# pulse-generator.net
KiCad netlist of a schematic drawn in EAGLE
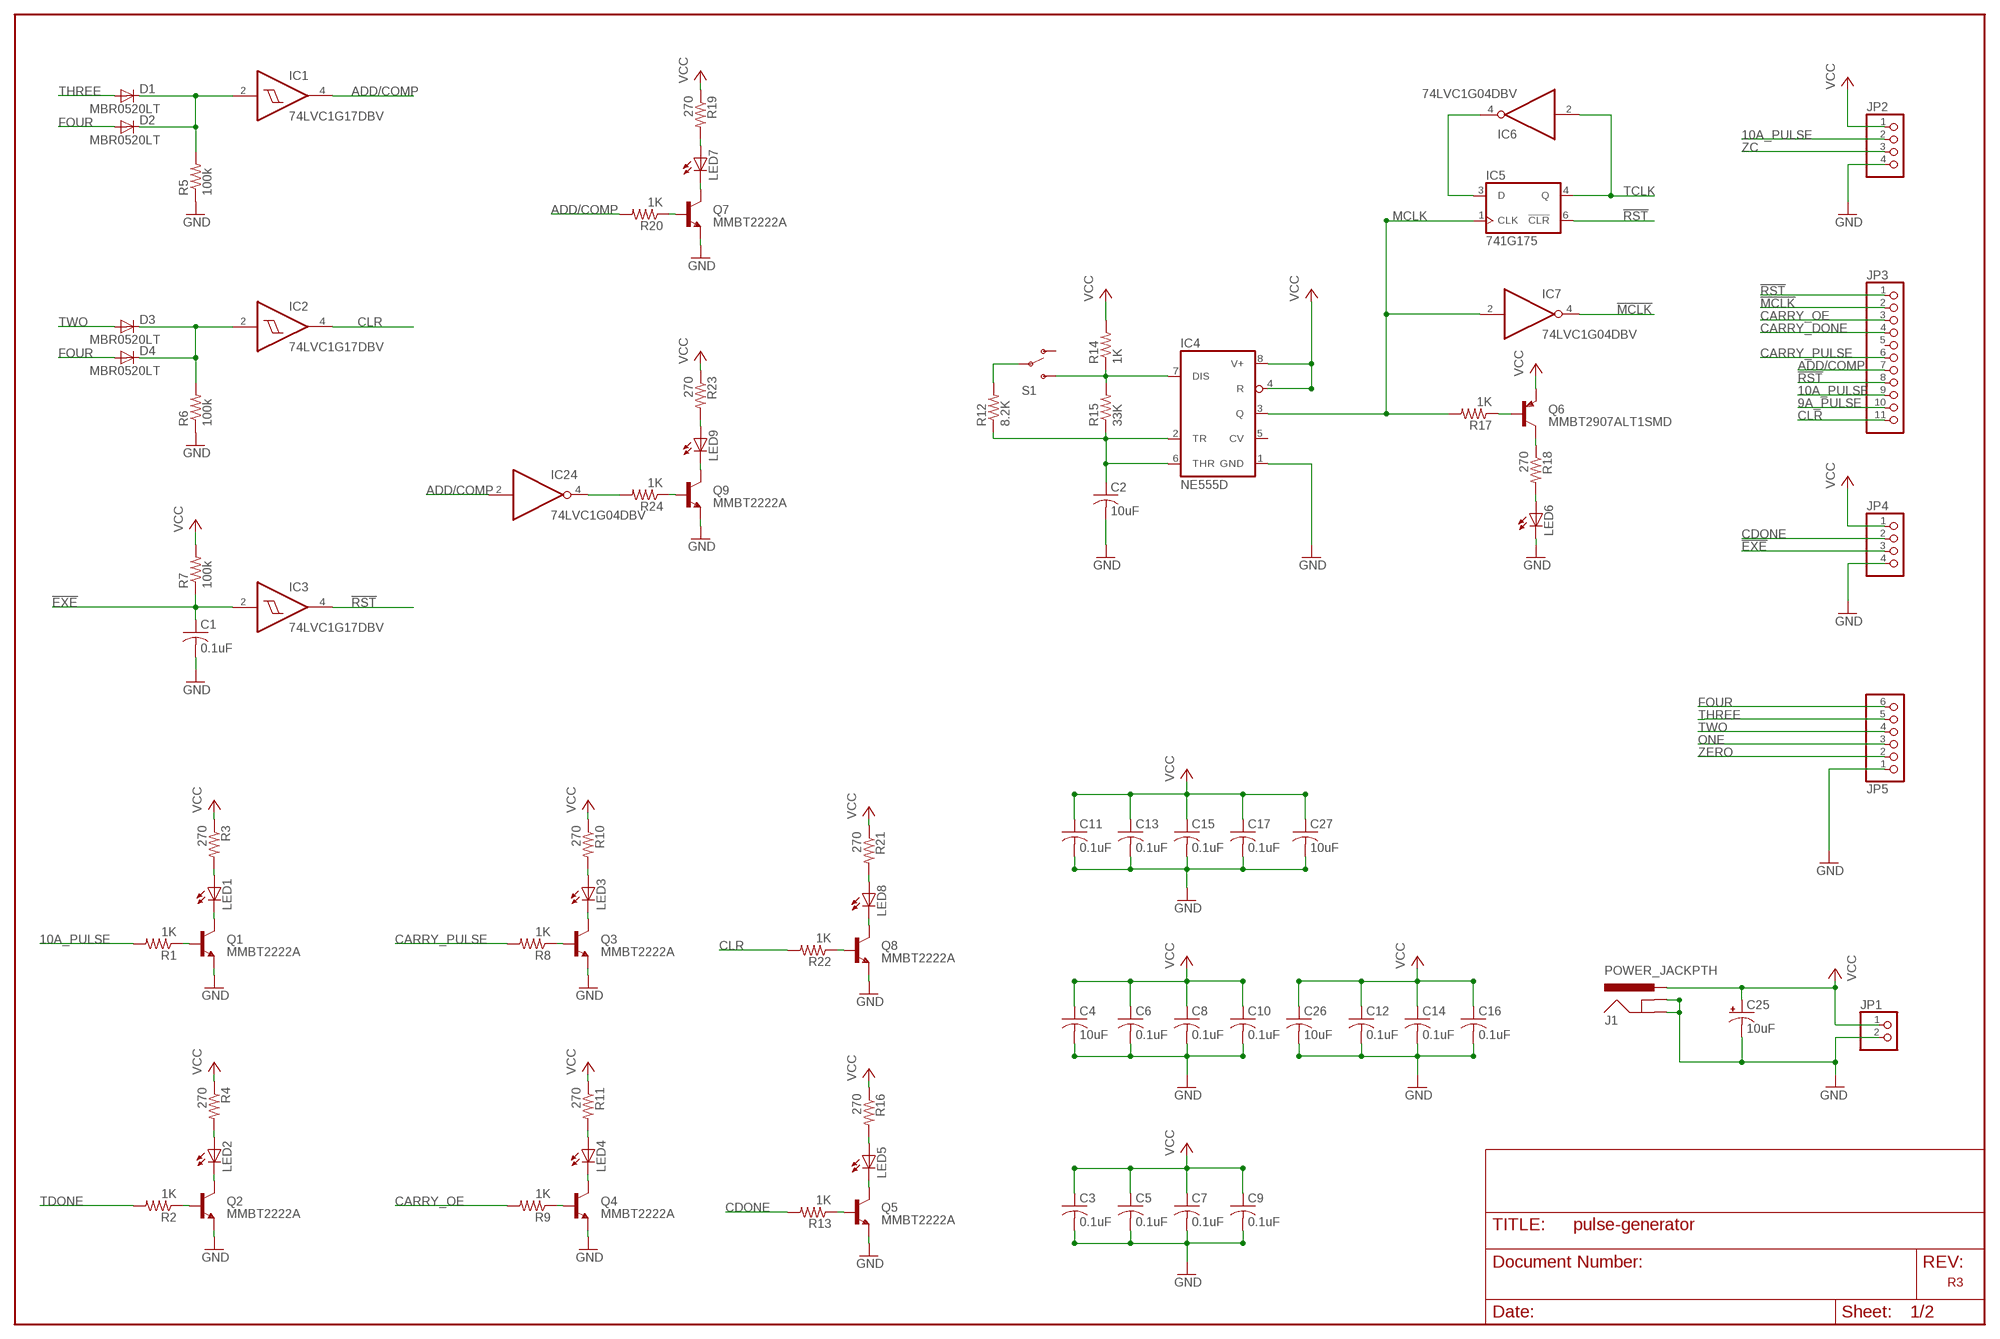
[diagram p0: schematic, sheet 1]
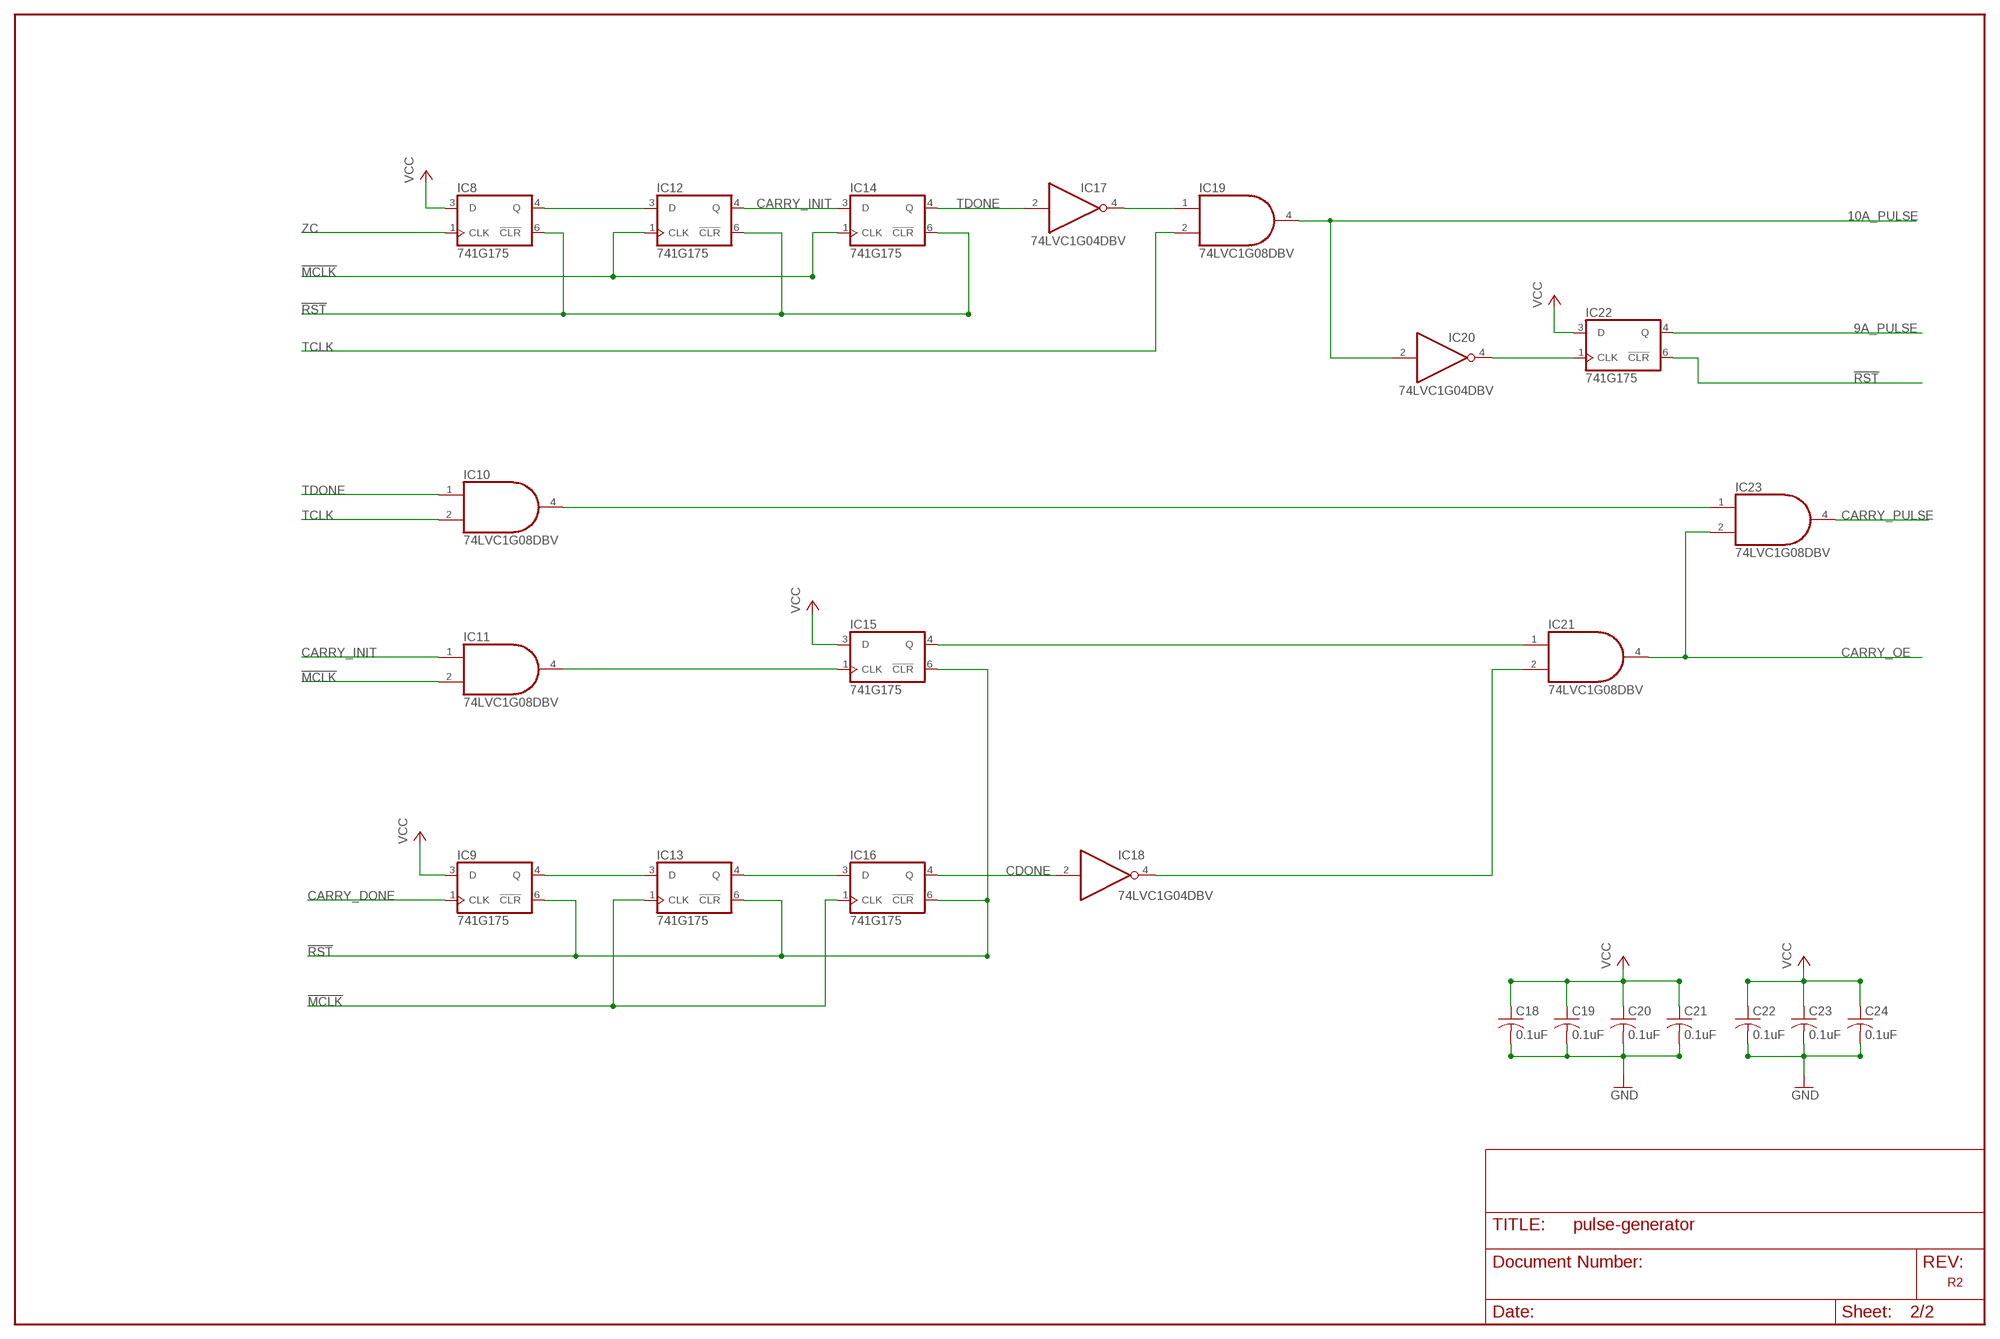
[diagram p1: schematic, sheet 2]

(export (version "E")
  (design (tool "Eeschema 10.0.6"))
  (components
    (comp (ref "C1")
      (value "0.1uF")
      (footprint "eagle-import:C0805")
      (libsource (lib "eagle-import") (part "C-USC0805"))
    )
    (comp (ref "C2")
      (value "10uF")
      (footprint "eagle-import:C0805")
      (libsource (lib "eagle-import") (part "C-USC0805"))
    )
    (comp (ref "C3")
      (value "0.1uF")
      (footprint "eagle-import:C0603")
      (libsource (lib "eagle-import") (part "C-USC0603"))
    )
    (comp (ref "C4")
      (value "10uF")
      (footprint "eagle-import:C0805")
      (libsource (lib "eagle-import") (part "C-USC0805"))
    )
    (comp (ref "C5")
      (value "0.1uF")
      (footprint "eagle-import:C0603")
      (libsource (lib "eagle-import") (part "C-USC0603"))
    )
    (comp (ref "C6")
      (value "0.1uF")
      (footprint "eagle-import:C0603")
      (libsource (lib "eagle-import") (part "C-USC0603"))
    )
    (comp (ref "C7")
      (value "0.1uF")
      (footprint "eagle-import:C0805")
      (libsource (lib "eagle-import") (part "C-USC0805"))
    )
    (comp (ref "C8")
      (value "0.1uF")
      (footprint "eagle-import:C0603")
      (libsource (lib "eagle-import") (part "C-USC0603"))
    )
    (comp (ref "C9")
      (value "0.1uF")
      (footprint "eagle-import:C0603")
      (libsource (lib "eagle-import") (part "C-USC0603"))
    )
    (comp (ref "C10")
      (value "0.1uF")
      (footprint "eagle-import:C0603")
      (libsource (lib "eagle-import") (part "C-USC0603"))
    )
    (comp (ref "C11")
      (value "0.1uF")
      (footprint "eagle-import:C0603")
      (libsource (lib "eagle-import") (part "C-USC0603"))
    )
    (comp (ref "C12")
      (value "0.1uF")
      (footprint "eagle-import:C0603")
      (libsource (lib "eagle-import") (part "C-USC0603"))
    )
    (comp (ref "C13")
      (value "0.1uF")
      (footprint "eagle-import:C0603")
      (libsource (lib "eagle-import") (part "C-USC0603"))
    )
    (comp (ref "C14")
      (value "0.1uF")
      (footprint "eagle-import:C0603")
      (libsource (lib "eagle-import") (part "C-USC0603"))
    )
    (comp (ref "C15")
      (value "0.1uF")
      (footprint "eagle-import:C0603")
      (libsource (lib "eagle-import") (part "C-USC0603"))
    )
    (comp (ref "C16")
      (value "0.1uF")
      (footprint "eagle-import:C0603")
      (libsource (lib "eagle-import") (part "C-USC0603"))
    )
    (comp (ref "C17")
      (value "0.1uF")
      (footprint "eagle-import:C0603")
      (libsource (lib "eagle-import") (part "C-USC0603"))
    )
    (comp (ref "C25")
      (value "10uF")
      (footprint "eagle-import:EIA3216")
      (libsource (lib "eagle-import") (part "10UF-16V-10%(TANT)"))
    )
    (comp (ref "C26")
      (value "10uF")
      (footprint "eagle-import:C0805")
      (libsource (lib "eagle-import") (part "C-USC0805"))
    )
    (comp (ref "C27")
      (value "10uF")
      (footprint "eagle-import:C0805")
      (libsource (lib "eagle-import") (part "C-USC0805"))
    )
    (comp (ref "D1")
      (value "MBR0520LT")
      (footprint "eagle-import:SOD123")
      (libsource (lib "eagle-import") (part "MBR0520LT"))
    )
    (comp (ref "D2")
      (value "MBR0520LT")
      (footprint "eagle-import:SOD123")
      (libsource (lib "eagle-import") (part "MBR0520LT"))
    )
    (comp (ref "D3")
      (value "MBR0520LT")
      (footprint "eagle-import:SOD123")
      (libsource (lib "eagle-import") (part "MBR0520LT"))
    )
    (comp (ref "D4")
      (value "MBR0520LT")
      (footprint "eagle-import:SOD123")
      (libsource (lib "eagle-import") (part "MBR0520LT"))
    )
    (comp (ref "IC1")
      (value "74LVC1G17DBV")
      (footprint "eagle-import:SOT23-5")
      (libsource (lib "eagle-import") (part "741G17DBVLVC"))
    )
    (comp (ref "IC2")
      (value "74LVC1G17DBV")
      (footprint "eagle-import:SOT23-5")
      (libsource (lib "eagle-import") (part "741G17DBVLVC"))
    )
    (comp (ref "IC3")
      (value "74LVC1G17DBV")
      (footprint "eagle-import:SOT23-5")
      (libsource (lib "eagle-import") (part "741G17DBVLVC"))
    )
    (comp (ref "IC4")
      (value "NE555D")
      (footprint "eagle-import:SO08")
      (libsource (lib "eagle-import") (part "555DNE"))
    )
    (comp (ref "IC5")
      (value "741G175")
      (footprint "eagle-import:DBV_R-PDSO-G6")
      (libsource (lib "eagle-import") (part "741G175"))
    )
    (comp (ref "IC6")
      (value "74LVC1G04DBV")
      (footprint "eagle-import:SOT23-5")
      (libsource (lib "eagle-import") (part "741G04DBVLVC"))
    )
    (comp (ref "IC7")
      (value "74LVC1G04DBV")
      (footprint "eagle-import:SOT23-5")
      (libsource (lib "eagle-import") (part "741G04DBVLVC"))
    )
    (comp (ref "IC24")
      (value "74LVC1G04DBV")
      (footprint "eagle-import:SOT23-5")
      (libsource (lib "eagle-import") (part "741G04DBVLVC"))
    )
    (comp (ref "J1")
      (value "POWER_JACKPTH")
      (footprint "eagle-import:POWER_JACK_PTH")
      (libsource (lib "eagle-import") (part "POWER_JACKPTH"))
    )
    (comp (ref "JP1")
      (value "PINHD-1X2")
      (footprint "eagle-import:1X02")
      (libsource (lib "eagle-import") (part "PINHD-1X2"))
    )
    (comp (ref "JP2")
      (value "PINHD-1X4")
      (footprint "eagle-import:1X04")
      (libsource (lib "eagle-import") (part "PINHD-1X4"))
    )
    (comp (ref "JP3")
      (value "PINHD-1X11")
      (footprint "eagle-import:1X11")
      (libsource (lib "eagle-import") (part "PINHD-1X11"))
    )
    (comp (ref "JP4")
      (value "PINHD-1X4")
      (footprint "eagle-import:1X04")
      (libsource (lib "eagle-import") (part "PINHD-1X4"))
    )
    (comp (ref "JP5")
      (value "PINHD-1X6")
      (footprint "eagle-import:1X06")
      (libsource (lib "eagle-import") (part "PINHD-1X6"))
    )
    (comp (ref "LED1")
      (value "LEDCHIP-LED0805")
      (footprint "eagle-import:CHIP-LED0805")
      (libsource (lib "eagle-import") (part "LEDCHIP-LED0805"))
    )
    (comp (ref "LED2")
      (value "LEDCHIP-LED0805")
      (footprint "eagle-import:CHIP-LED0805")
      (libsource (lib "eagle-import") (part "LEDCHIP-LED0805"))
    )
    (comp (ref "LED3")
      (value "LEDCHIP-LED0805")
      (footprint "eagle-import:CHIP-LED0805")
      (libsource (lib "eagle-import") (part "LEDCHIP-LED0805"))
    )
    (comp (ref "LED4")
      (value "LEDCHIP-LED0805")
      (footprint "eagle-import:CHIP-LED0805")
      (libsource (lib "eagle-import") (part "LEDCHIP-LED0805"))
    )
    (comp (ref "LED5")
      (value "LEDCHIP-LED0805")
      (footprint "eagle-import:CHIP-LED0805")
      (libsource (lib "eagle-import") (part "LEDCHIP-LED0805"))
    )
    (comp (ref "LED6")
      (value "LEDCHIP-LED0805")
      (footprint "eagle-import:CHIP-LED0805")
      (libsource (lib "eagle-import") (part "LEDCHIP-LED0805"))
    )
    (comp (ref "LED7")
      (value "LEDCHIP-LED0805")
      (footprint "eagle-import:CHIP-LED0805")
      (libsource (lib "eagle-import") (part "LEDCHIP-LED0805"))
    )
    (comp (ref "LED8")
      (value "LEDCHIP-LED0805")
      (footprint "eagle-import:CHIP-LED0805")
      (libsource (lib "eagle-import") (part "LEDCHIP-LED0805"))
    )
    (comp (ref "LED9")
      (value "LEDCHIP-LED0805")
      (footprint "eagle-import:CHIP-LED0805")
      (libsource (lib "eagle-import") (part "LEDCHIP-LED0805"))
    )
    (comp (ref "Q1")
      (value "MMBT2222A")
      (footprint "eagle-import:SOT23-3")
      (libsource (lib "eagle-import") (part "TRANSISTOR_NPNMMBT2222A"))
    )
    (comp (ref "Q2")
      (value "MMBT2222A")
      (footprint "eagle-import:SOT23-3")
      (libsource (lib "eagle-import") (part "TRANSISTOR_NPNMMBT2222A"))
    )
    (comp (ref "Q3")
      (value "MMBT2222A")
      (footprint "eagle-import:SOT23-3")
      (libsource (lib "eagle-import") (part "TRANSISTOR_NPNMMBT2222A"))
    )
    (comp (ref "Q4")
      (value "MMBT2222A")
      (footprint "eagle-import:SOT23-3")
      (libsource (lib "eagle-import") (part "TRANSISTOR_NPNMMBT2222A"))
    )
    (comp (ref "Q5")
      (value "MMBT2222A")
      (footprint "eagle-import:SOT23-3")
      (libsource (lib "eagle-import") (part "TRANSISTOR_NPNMMBT2222A"))
    )
    (comp (ref "Q6")
      (value "MMBT2907ALT1SMD")
      (footprint "eagle-import:SOT23-BEC")
      (libsource (lib "eagle-import") (part "MMBT2907SMDALT1"))
    )
    (comp (ref "Q7")
      (value "MMBT2222A")
      (footprint "eagle-import:SOT23-3")
      (libsource (lib "eagle-import") (part "TRANSISTOR_NPNMMBT2222A"))
    )
    (comp (ref "Q8")
      (value "MMBT2222A")
      (footprint "eagle-import:SOT23-3")
      (libsource (lib "eagle-import") (part "TRANSISTOR_NPNMMBT2222A"))
    )
    (comp (ref "Q9")
      (value "MMBT2222A")
      (footprint "eagle-import:SOT23-3")
      (libsource (lib "eagle-import") (part "TRANSISTOR_NPNMMBT2222A"))
    )
    (comp (ref "R1")
      (value "1K")
      (footprint "eagle-import:R0805")
      (libsource (lib "eagle-import") (part "R-US_R0805"))
    )
    (comp (ref "R2")
      (value "1K")
      (footprint "eagle-import:R0805")
      (libsource (lib "eagle-import") (part "R-US_R0805"))
    )
    (comp (ref "R3")
      (value "270")
      (footprint "eagle-import:R0805")
      (libsource (lib "eagle-import") (part "R-US_R0805"))
    )
    (comp (ref "R4")
      (value "270")
      (footprint "eagle-import:R0805")
      (libsource (lib "eagle-import") (part "R-US_R0805"))
    )
    (comp (ref "R5")
      (value "100k")
      (footprint "eagle-import:R0805")
      (libsource (lib "eagle-import") (part "R-US_R0805"))
    )
    (comp (ref "R6")
      (value "100k")
      (footprint "eagle-import:R0805")
      (libsource (lib "eagle-import") (part "R-US_R0805"))
    )
    (comp (ref "R7")
      (value "100k")
      (footprint "eagle-import:R0805")
      (libsource (lib "eagle-import") (part "R-US_R0805"))
    )
    (comp (ref "R8")
      (value "1K")
      (footprint "eagle-import:R0805")
      (libsource (lib "eagle-import") (part "R-US_R0805"))
    )
    (comp (ref "R9")
      (value "1K")
      (footprint "eagle-import:R0805")
      (libsource (lib "eagle-import") (part "R-US_R0805"))
    )
    (comp (ref "R10")
      (value "270")
      (footprint "eagle-import:R0805")
      (libsource (lib "eagle-import") (part "R-US_R0805"))
    )
    (comp (ref "R11")
      (value "270")
      (footprint "eagle-import:R0805")
      (libsource (lib "eagle-import") (part "R-US_R0805"))
    )
    (comp (ref "R12")
      (value "8.2K")
      (footprint "eagle-import:R0805")
      (libsource (lib "eagle-import") (part "R-US_R0805"))
    )
    (comp (ref "R13")
      (value "1K")
      (footprint "eagle-import:R0805")
      (libsource (lib "eagle-import") (part "R-US_R0805"))
    )
    (comp (ref "R14")
      (value "1K")
      (footprint "eagle-import:R0805")
      (libsource (lib "eagle-import") (part "R-US_R0805"))
    )
    (comp (ref "R15")
      (value "33K")
      (footprint "eagle-import:R0805")
      (libsource (lib "eagle-import") (part "R-US_R0805"))
    )
    (comp (ref "R16")
      (value "270")
      (footprint "eagle-import:R0805")
      (libsource (lib "eagle-import") (part "R-US_R0805"))
    )
    (comp (ref "R17")
      (value "1K")
      (footprint "eagle-import:R0805")
      (libsource (lib "eagle-import") (part "R-US_R0805"))
    )
    (comp (ref "R18")
      (value "270")
      (footprint "eagle-import:R0805")
      (libsource (lib "eagle-import") (part "R-US_R0805"))
    )
    (comp (ref "R19")
      (value "270")
      (footprint "eagle-import:R0805")
      (libsource (lib "eagle-import") (part "R-US_R0805"))
    )
    (comp (ref "R20")
      (value "1K")
      (footprint "eagle-import:R0805")
      (libsource (lib "eagle-import") (part "R-US_R0805"))
    )
    (comp (ref "R21")
      (value "270")
      (footprint "eagle-import:R0805")
      (libsource (lib "eagle-import") (part "R-US_R0805"))
    )
    (comp (ref "R22")
      (value "1K")
      (footprint "eagle-import:R0805")
      (libsource (lib "eagle-import") (part "R-US_R0805"))
    )
    (comp (ref "R23")
      (value "270")
      (footprint "eagle-import:R0805")
      (libsource (lib "eagle-import") (part "R-US_R0805"))
    )
    (comp (ref "R24")
      (value "1K")
      (footprint "eagle-import:R0805")
      (libsource (lib "eagle-import") (part "R-US_R0805"))
    )
    (comp (ref "S1")
      (value "SWITCH-SPDTPTH")
      (footprint "eagle-import:SWITCH-SPDT")
      (libsource (lib "eagle-import") (part "SWITCH-SPDTPTH"))
    )
    (comp (ref "C18")
      (value "0.1uF")
      (footprint "eagle-import:C0603")
      (libsource (lib "eagle-import") (part "C-USC0603"))
    )
    (comp (ref "C19")
      (value "0.1uF")
      (footprint "eagle-import:C0603")
      (libsource (lib "eagle-import") (part "C-USC0603"))
    )
    (comp (ref "C20")
      (value "0.1uF")
      (footprint "eagle-import:C0603")
      (libsource (lib "eagle-import") (part "C-USC0603"))
    )
    (comp (ref "C21")
      (value "0.1uF")
      (footprint "eagle-import:C0603")
      (libsource (lib "eagle-import") (part "C-USC0603"))
    )
    (comp (ref "C22")
      (value "0.1uF")
      (footprint "eagle-import:C0603")
      (libsource (lib "eagle-import") (part "C-USC0603"))
    )
    (comp (ref "C23")
      (value "0.1uF")
      (footprint "eagle-import:C0603")
      (libsource (lib "eagle-import") (part "C-USC0603"))
    )
    (comp (ref "C24")
      (value "0.1uF")
      (footprint "eagle-import:C0603")
      (libsource (lib "eagle-import") (part "C-USC0603"))
    )
    (comp (ref "IC8")
      (value "741G175")
      (footprint "eagle-import:DBV_R-PDSO-G6")
      (libsource (lib "eagle-import") (part "741G175"))
    )
    (comp (ref "IC9")
      (value "741G175")
      (footprint "eagle-import:DBV_R-PDSO-G6")
      (libsource (lib "eagle-import") (part "741G175"))
    )
    (comp (ref "IC10")
      (value "74LVC1G08DBV")
      (footprint "eagle-import:SOT23-5")
      (libsource (lib "eagle-import") (part "741G08DBVLVC"))
    )
    (comp (ref "IC11")
      (value "74LVC1G08DBV")
      (footprint "eagle-import:SOT23-5")
      (libsource (lib "eagle-import") (part "741G08DBVLVC"))
    )
    (comp (ref "IC12")
      (value "741G175")
      (footprint "eagle-import:DBV_R-PDSO-G6")
      (libsource (lib "eagle-import") (part "741G175"))
    )
    (comp (ref "IC13")
      (value "741G175")
      (footprint "eagle-import:DBV_R-PDSO-G6")
      (libsource (lib "eagle-import") (part "741G175"))
    )
    (comp (ref "IC14")
      (value "741G175")
      (footprint "eagle-import:DBV_R-PDSO-G6")
      (libsource (lib "eagle-import") (part "741G175"))
    )
    (comp (ref "IC15")
      (value "741G175")
      (footprint "eagle-import:DBV_R-PDSO-G6")
      (libsource (lib "eagle-import") (part "741G175"))
    )
    (comp (ref "IC16")
      (value "741G175")
      (footprint "eagle-import:DBV_R-PDSO-G6")
      (libsource (lib "eagle-import") (part "741G175"))
    )
    (comp (ref "IC17")
      (value "74LVC1G04DBV")
      (footprint "eagle-import:SOT23-5")
      (libsource (lib "eagle-import") (part "741G04DBVLVC"))
    )
    (comp (ref "IC18")
      (value "74LVC1G04DBV")
      (footprint "eagle-import:SOT23-5")
      (libsource (lib "eagle-import") (part "741G04DBVLVC"))
    )
    (comp (ref "IC19")
      (value "74LVC1G08DBV")
      (footprint "eagle-import:SOT23-5")
      (libsource (lib "eagle-import") (part "741G08DBVLVC"))
    )
    (comp (ref "IC20")
      (value "74LVC1G04DBV")
      (footprint "eagle-import:SOT23-5")
      (libsource (lib "eagle-import") (part "741G04DBVLVC"))
    )
    (comp (ref "IC21")
      (value "74LVC1G08DBV")
      (footprint "eagle-import:SOT23-5")
      (libsource (lib "eagle-import") (part "741G08DBVLVC"))
    )
    (comp (ref "IC22")
      (value "741G175")
      (footprint "eagle-import:DBV_R-PDSO-G6")
      (libsource (lib "eagle-import") (part "741G175"))
    )
    (comp (ref "IC23")
      (value "74LVC1G08DBV")
      (footprint "eagle-import:SOT23-5")
      (libsource (lib "eagle-import") (part "741G08DBVLVC"))
    )
  )
  (nets
    (net (code "1") (name "9A_PULSE") (class "Default")
      (node (ref "IC22") (pin "4") (pinfunction "Q_4") (pintype "output"))
      (node (ref "JP3") (pin "10") (pinfunction "10_10") (pintype "passive"))
    )
    (net (code "2") (name "10A_PULSE") (class "Default")
      (node (ref "IC19") (pin "4") (pinfunction "O_4") (pintype "output"))
      (node (ref "IC20") (pin "2") (pinfunction "I_2") (pintype "input"))
      (node (ref "JP2") (pin "2") (pinfunction "2_2") (pintype "passive"))
      (node (ref "JP3") (pin "9") (pinfunction "9_9") (pintype "passive"))
      (node (ref "R1") (pin "2") (pinfunction "2_2") (pintype "passive"))
    )
    (net (code "3") (name "ADD{slash}COMP") (class "Default")
      (node (ref "IC1") (pin "4") (pinfunction "O_4") (pintype "output"))
      (node (ref "IC24") (pin "2") (pinfunction "I_2") (pintype "input"))
      (node (ref "JP3") (pin "7") (pinfunction "7_7") (pintype "passive"))
      (node (ref "R20") (pin "2") (pinfunction "2_2") (pintype "passive"))
    )
    (net (code "4") (name "CARRY_DONE") (class "Default")
      (node (ref "IC9") (pin "1") (pinfunction "CLK_1") (pintype "input"))
      (node (ref "JP3") (pin "4") (pinfunction "4_4") (pintype "passive"))
    )
    (net (code "5") (name "CARRY_INIT") (class "Default")
      (node (ref "IC11") (pin "1") (pinfunction "I0_1") (pintype "input"))
      (node (ref "IC12") (pin "4") (pinfunction "Q_4") (pintype "output"))
      (node (ref "IC14") (pin "3") (pinfunction "D_3") (pintype "input"))
    )
    (net (code "6") (name "CARRY_OE") (class "Default")
      (node (ref "IC21") (pin "4") (pinfunction "O_4") (pintype "output"))
      (node (ref "IC23") (pin "2") (pinfunction "I1_2") (pintype "input"))
      (node (ref "JP3") (pin "3") (pinfunction "3_3") (pintype "passive"))
      (node (ref "R9") (pin "2") (pinfunction "2_2") (pintype "passive"))
    )
    (net (code "7") (name "CARRY_PULSE") (class "Default")
      (node (ref "IC23") (pin "4") (pinfunction "O_4") (pintype "output"))
      (node (ref "JP3") (pin "6") (pinfunction "6_6") (pintype "passive"))
      (node (ref "R8") (pin "2") (pinfunction "2_2") (pintype "passive"))
    )
    (net (code "8") (name "CDONE") (class "Default")
      (node (ref "IC16") (pin "4") (pinfunction "Q_4") (pintype "output"))
      (node (ref "IC18") (pin "2") (pinfunction "I_2") (pintype "input"))
      (node (ref "JP4") (pin "2") (pinfunction "2_2") (pintype "passive"))
      (node (ref "R13") (pin "2") (pinfunction "2_2") (pintype "passive"))
    )
    (net (code "9") (name "CLR") (class "Default")
      (node (ref "IC2") (pin "4") (pinfunction "O_4") (pintype "output"))
      (node (ref "JP3") (pin "11") (pinfunction "11_11") (pintype "passive"))
      (node (ref "R22") (pin "2") (pinfunction "2_2") (pintype "passive"))
    )
    (net (code "10") (name "FOUR") (class "Default")
      (node (ref "D2") (pin "A") (pinfunction "A_A") (pintype "passive"))
      (node (ref "D4") (pin "A") (pinfunction "A_A") (pintype "passive"))
      (node (ref "JP5") (pin "6") (pinfunction "6_6") (pintype "passive"))
    )
    (net (code "11") (name "GND") (class "Default")
      (node (ref "C1") (pin "2") (pinfunction "2_2") (pintype "passive"))
      (node (ref "C10") (pin "2") (pinfunction "2_2") (pintype "passive"))
      (node (ref "C11") (pin "2") (pinfunction "2_2") (pintype "passive"))
      (node (ref "C12") (pin "2") (pinfunction "2_2") (pintype "passive"))
      (node (ref "C13") (pin "2") (pinfunction "2_2") (pintype "passive"))
      (node (ref "C14") (pin "2") (pinfunction "2_2") (pintype "passive"))
      (node (ref "C15") (pin "2") (pinfunction "2_2") (pintype "passive"))
      (node (ref "C16") (pin "2") (pinfunction "2_2") (pintype "passive"))
      (node (ref "C17") (pin "2") (pinfunction "2_2") (pintype "passive"))
      (node (ref "C18") (pin "2") (pinfunction "2_2") (pintype "passive"))
      (node (ref "C19") (pin "2") (pinfunction "2_2") (pintype "passive"))
      (node (ref "C2") (pin "2") (pinfunction "2_2") (pintype "passive"))
      (node (ref "C20") (pin "2") (pinfunction "2_2") (pintype "passive"))
      (node (ref "C21") (pin "2") (pinfunction "2_2") (pintype "passive"))
      (node (ref "C22") (pin "2") (pinfunction "2_2") (pintype "passive"))
      (node (ref "C23") (pin "2") (pinfunction "2_2") (pintype "passive"))
      (node (ref "C24") (pin "2") (pinfunction "2_2") (pintype "passive"))
      (node (ref "C25") (pin "C") (pinfunction "-_C") (pintype "passive"))
      (node (ref "C26") (pin "2") (pinfunction "2_2") (pintype "passive"))
      (node (ref "C27") (pin "2") (pinfunction "2_2") (pintype "passive"))
      (node (ref "C3") (pin "2") (pinfunction "2_2") (pintype "passive"))
      (node (ref "C4") (pin "2") (pinfunction "2_2") (pintype "passive"))
      (node (ref "C5") (pin "2") (pinfunction "2_2") (pintype "passive"))
      (node (ref "C6") (pin "2") (pinfunction "2_2") (pintype "passive"))
      (node (ref "C7") (pin "2") (pinfunction "2_2") (pintype "passive"))
      (node (ref "C8") (pin "2") (pinfunction "2_2") (pintype "passive"))
      (node (ref "C9") (pin "2") (pinfunction "2_2") (pintype "passive"))
      (node (ref "IC4") (pin "1") (pinfunction "GND_1") (pintype "power_in"))
      (node (ref "J1") (pin "GND") (pinfunction "GND_GND") (pintype "bidirectional"))
      (node (ref "J1") (pin "GNDBREAK") (pinfunction "GNDBREAK_GNDBREAK") (pintype "bidirectional"))
      (node (ref "JP1") (pin "2") (pinfunction "2_2") (pintype "passive"))
      (node (ref "JP2") (pin "4") (pinfunction "4_4") (pintype "passive"))
      (node (ref "JP4") (pin "4") (pinfunction "4_4") (pintype "passive"))
      (node (ref "JP5") (pin "1") (pinfunction "1_1") (pintype "passive"))
      (node (ref "LED6") (pin "C") (pinfunction "C_C") (pintype "passive"))
      (node (ref "Q1") (pin "2") (pinfunction "E_2") (pintype "passive"))
      (node (ref "Q2") (pin "2") (pinfunction "E_2") (pintype "passive"))
      (node (ref "Q3") (pin "2") (pinfunction "E_2") (pintype "passive"))
      (node (ref "Q4") (pin "2") (pinfunction "E_2") (pintype "passive"))
      (node (ref "Q5") (pin "2") (pinfunction "E_2") (pintype "passive"))
      (node (ref "Q7") (pin "2") (pinfunction "E_2") (pintype "passive"))
      (node (ref "Q8") (pin "2") (pinfunction "E_2") (pintype "passive"))
      (node (ref "Q9") (pin "2") (pinfunction "E_2") (pintype "passive"))
      (node (ref "R5") (pin "1") (pinfunction "1_1") (pintype "passive"))
      (node (ref "R6") (pin "1") (pinfunction "1_1") (pintype "passive"))
    )
    (net (code "12") (name "MCLK") (class "Default")
      (node (ref "IC4") (pin "3") (pinfunction "Q_3") (pintype "output"))
      (node (ref "IC5") (pin "1") (pinfunction "CLK_1") (pintype "input"))
      (node (ref "IC7") (pin "2") (pinfunction "I_2") (pintype "input"))
      (node (ref "R17") (pin "2") (pinfunction "2_2") (pintype "passive"))
    )
    (net (code "13") (name "Net-(IC1A-I)") (class "Default")
      (node (ref "D1") (pin "C") (pinfunction "C_C") (pintype "passive"))
      (node (ref "D2") (pin "C") (pinfunction "C_C") (pintype "passive"))
      (node (ref "IC1") (pin "2") (pinfunction "I_2") (pintype "input"))
      (node (ref "R5") (pin "2") (pinfunction "2_2") (pintype "passive"))
    )
    (net (code "14") (name "Net-(IC2A-I)") (class "Default")
      (node (ref "D3") (pin "C") (pinfunction "C_C") (pintype "passive"))
      (node (ref "D4") (pin "C") (pinfunction "C_C") (pintype "passive"))
      (node (ref "IC2") (pin "2") (pinfunction "I_2") (pintype "input"))
      (node (ref "R6") (pin "2") (pinfunction "2_2") (pintype "passive"))
    )
    (net (code "15") (name "Net-(IC4-DIS)") (class "Default")
      (node (ref "IC4") (pin "7") (pinfunction "DIS_7") (pintype "input"))
      (node (ref "R14") (pin "1") (pinfunction "1_1") (pintype "passive"))
      (node (ref "R15") (pin "2") (pinfunction "2_2") (pintype "passive"))
      (node (ref "S1") (pin "3") (pinfunction "S_3") (pintype "passive"))
    )
    (net (code "16") (name "Net-(IC4-THR)") (class "Default")
      (node (ref "C2") (pin "1") (pinfunction "1_1") (pintype "passive"))
      (node (ref "IC4") (pin "2") (pinfunction "TR_2") (pintype "input"))
      (node (ref "IC4") (pin "6") (pinfunction "THR_6") (pintype "input"))
      (node (ref "R12") (pin "1") (pinfunction "1_1") (pintype "passive"))
      (node (ref "R15") (pin "1") (pinfunction "1_1") (pintype "passive"))
    )
    (net (code "17") (name "Net-(IC5A-D)") (class "Default")
      (node (ref "IC5") (pin "3") (pinfunction "D_3") (pintype "input"))
      (node (ref "IC6") (pin "4") (pinfunction "O_4") (pintype "output"))
    )
    (net (code "18") (name "Net-(IC10A-O)") (class "Default")
      (node (ref "IC10") (pin "4") (pinfunction "O_4") (pintype "output"))
      (node (ref "IC23") (pin "1") (pinfunction "I0_1") (pintype "input"))
    )
    (net (code "19") (name "Net-(IC11A-O)") (class "Default")
      (node (ref "IC11") (pin "4") (pinfunction "O_4") (pintype "output"))
      (node (ref "IC15") (pin "1") (pinfunction "CLK_1") (pintype "input"))
    )
    (net (code "20") (name "Net-(IC12A-D)") (class "Default")
      (node (ref "IC12") (pin "3") (pinfunction "D_3") (pintype "input"))
      (node (ref "IC8") (pin "4") (pinfunction "Q_4") (pintype "output"))
    )
    (net (code "21") (name "Net-(IC13A-D)") (class "Default")
      (node (ref "IC13") (pin "3") (pinfunction "D_3") (pintype "input"))
      (node (ref "IC9") (pin "4") (pinfunction "Q_4") (pintype "output"))
    )
    (net (code "22") (name "Net-(IC13A-Q)") (class "Default")
      (node (ref "IC13") (pin "4") (pinfunction "Q_4") (pintype "output"))
      (node (ref "IC16") (pin "3") (pinfunction "D_3") (pintype "input"))
    )
    (net (code "23") (name "Net-(IC15A-Q)") (class "Default")
      (node (ref "IC15") (pin "4") (pinfunction "Q_4") (pintype "output"))
      (node (ref "IC21") (pin "1") (pinfunction "I0_1") (pintype "input"))
    )
    (net (code "24") (name "Net-(IC17A-O)") (class "Default")
      (node (ref "IC17") (pin "4") (pinfunction "O_4") (pintype "output"))
      (node (ref "IC19") (pin "1") (pinfunction "I0_1") (pintype "input"))
    )
    (net (code "25") (name "Net-(IC18A-O)") (class "Default")
      (node (ref "IC18") (pin "4") (pinfunction "O_4") (pintype "output"))
      (node (ref "IC21") (pin "2") (pinfunction "I1_2") (pintype "input"))
    )
    (net (code "26") (name "Net-(IC20A-O)") (class "Default")
      (node (ref "IC20") (pin "4") (pinfunction "O_4") (pintype "output"))
      (node (ref "IC22") (pin "1") (pinfunction "CLK_1") (pintype "input"))
    )
    (net (code "27") (name "Net-(IC24A-O)") (class "Default")
      (node (ref "IC24") (pin "4") (pinfunction "O_4") (pintype "output"))
      (node (ref "R24") (pin "2") (pinfunction "2_2") (pintype "passive"))
    )
    (net (code "28") (name "Net-(LED1-PadA)") (class "Default")
      (node (ref "LED1") (pin "A") (pinfunction "A_A") (pintype "passive"))
      (node (ref "R3") (pin "2") (pinfunction "2_2") (pintype "passive"))
    )
    (net (code "29") (name "Net-(LED2-PadA)") (class "Default")
      (node (ref "LED2") (pin "A") (pinfunction "A_A") (pintype "passive"))
      (node (ref "R4") (pin "2") (pinfunction "2_2") (pintype "passive"))
    )
    (net (code "30") (name "Net-(LED3-PadA)") (class "Default")
      (node (ref "LED3") (pin "A") (pinfunction "A_A") (pintype "passive"))
      (node (ref "R10") (pin "2") (pinfunction "2_2") (pintype "passive"))
    )
    (net (code "31") (name "Net-(LED4-PadA)") (class "Default")
      (node (ref "LED4") (pin "A") (pinfunction "A_A") (pintype "passive"))
      (node (ref "R11") (pin "2") (pinfunction "2_2") (pintype "passive"))
    )
    (net (code "32") (name "Net-(LED5-PadA)") (class "Default")
      (node (ref "LED5") (pin "A") (pinfunction "A_A") (pintype "passive"))
      (node (ref "R16") (pin "2") (pinfunction "2_2") (pintype "passive"))
    )
    (net (code "33") (name "Net-(LED6-PadA)") (class "Default")
      (node (ref "LED6") (pin "A") (pinfunction "A_A") (pintype "passive"))
      (node (ref "R18") (pin "2") (pinfunction "2_2") (pintype "passive"))
    )
    (net (code "34") (name "Net-(LED7-PadA)") (class "Default")
      (node (ref "LED7") (pin "A") (pinfunction "A_A") (pintype "passive"))
      (node (ref "R19") (pin "2") (pinfunction "2_2") (pintype "passive"))
    )
    (net (code "35") (name "Net-(LED8-PadA)") (class "Default")
      (node (ref "LED8") (pin "A") (pinfunction "A_A") (pintype "passive"))
      (node (ref "R21") (pin "2") (pinfunction "2_2") (pintype "passive"))
    )
    (net (code "36") (name "Net-(LED9-PadA)") (class "Default")
      (node (ref "LED9") (pin "A") (pinfunction "A_A") (pintype "passive"))
      (node (ref "R23") (pin "2") (pinfunction "2_2") (pintype "passive"))
    )
    (net (code "37") (name "Net-(Q1-B)") (class "Default")
      (node (ref "Q1") (pin "1") (pinfunction "B_1") (pintype "passive"))
      (node (ref "R1") (pin "1") (pinfunction "1_1") (pintype "passive"))
    )
    (net (code "38") (name "Net-(Q1-C)") (class "Default")
      (node (ref "LED1") (pin "C") (pinfunction "C_C") (pintype "passive"))
      (node (ref "Q1") (pin "3") (pinfunction "C_3") (pintype "passive"))
    )
    (net (code "39") (name "Net-(Q2-B)") (class "Default")
      (node (ref "Q2") (pin "1") (pinfunction "B_1") (pintype "passive"))
      (node (ref "R2") (pin "1") (pinfunction "1_1") (pintype "passive"))
    )
    (net (code "40") (name "Net-(Q2-C)") (class "Default")
      (node (ref "LED2") (pin "C") (pinfunction "C_C") (pintype "passive"))
      (node (ref "Q2") (pin "3") (pinfunction "C_3") (pintype "passive"))
    )
    (net (code "41") (name "Net-(Q3-B)") (class "Default")
      (node (ref "Q3") (pin "1") (pinfunction "B_1") (pintype "passive"))
      (node (ref "R8") (pin "1") (pinfunction "1_1") (pintype "passive"))
    )
    (net (code "42") (name "Net-(Q3-C)") (class "Default")
      (node (ref "LED3") (pin "C") (pinfunction "C_C") (pintype "passive"))
      (node (ref "Q3") (pin "3") (pinfunction "C_3") (pintype "passive"))
    )
    (net (code "43") (name "Net-(Q4-B)") (class "Default")
      (node (ref "Q4") (pin "1") (pinfunction "B_1") (pintype "passive"))
      (node (ref "R9") (pin "1") (pinfunction "1_1") (pintype "passive"))
    )
    (net (code "44") (name "Net-(Q4-C)") (class "Default")
      (node (ref "LED4") (pin "C") (pinfunction "C_C") (pintype "passive"))
      (node (ref "Q4") (pin "3") (pinfunction "C_3") (pintype "passive"))
    )
    (net (code "45") (name "Net-(Q5-B)") (class "Default")
      (node (ref "Q5") (pin "1") (pinfunction "B_1") (pintype "passive"))
      (node (ref "R13") (pin "1") (pinfunction "1_1") (pintype "passive"))
    )
    (net (code "46") (name "Net-(Q5-C)") (class "Default")
      (node (ref "LED5") (pin "C") (pinfunction "C_C") (pintype "passive"))
      (node (ref "Q5") (pin "3") (pinfunction "C_3") (pintype "passive"))
    )
    (net (code "47") (name "Net-(Q6-PadB)") (class "Default")
      (node (ref "Q6") (pin "B") (pinfunction "B_B") (pintype "passive"))
      (node (ref "R17") (pin "1") (pinfunction "1_1") (pintype "passive"))
    )
    (net (code "48") (name "Net-(Q6-PadC)") (class "Default")
      (node (ref "Q6") (pin "C") (pinfunction "C_C") (pintype "passive"))
      (node (ref "R18") (pin "1") (pinfunction "1_1") (pintype "passive"))
    )
    (net (code "49") (name "Net-(Q7-B)") (class "Default")
      (node (ref "Q7") (pin "1") (pinfunction "B_1") (pintype "passive"))
      (node (ref "R20") (pin "1") (pinfunction "1_1") (pintype "passive"))
    )
    (net (code "50") (name "Net-(Q7-C)") (class "Default")
      (node (ref "LED7") (pin "C") (pinfunction "C_C") (pintype "passive"))
      (node (ref "Q7") (pin "3") (pinfunction "C_3") (pintype "passive"))
    )
    (net (code "51") (name "Net-(Q8-B)") (class "Default")
      (node (ref "Q8") (pin "1") (pinfunction "B_1") (pintype "passive"))
      (node (ref "R22") (pin "1") (pinfunction "1_1") (pintype "passive"))
    )
    (net (code "52") (name "Net-(Q8-C)") (class "Default")
      (node (ref "LED8") (pin "C") (pinfunction "C_C") (pintype "passive"))
      (node (ref "Q8") (pin "3") (pinfunction "C_3") (pintype "passive"))
    )
    (net (code "53") (name "Net-(Q9-B)") (class "Default")
      (node (ref "Q9") (pin "1") (pinfunction "B_1") (pintype "passive"))
      (node (ref "R24") (pin "1") (pinfunction "1_1") (pintype "passive"))
    )
    (net (code "54") (name "Net-(Q9-C)") (class "Default")
      (node (ref "LED9") (pin "C") (pinfunction "C_C") (pintype "passive"))
      (node (ref "Q9") (pin "3") (pinfunction "C_3") (pintype "passive"))
    )
    (net (code "55") (name "Net-(S1-P)") (class "Default")
      (node (ref "R12") (pin "2") (pinfunction "2_2") (pintype "passive"))
      (node (ref "S1") (pin "2") (pinfunction "P_2") (pintype "passive"))
    )
    (net (code "56") (name "ONE") (class "Default")
      (node (ref "JP5") (pin "3") (pinfunction "3_3") (pintype "passive"))
    )
    (net (code "57") (name "TCLK") (class "Default")
      (node (ref "IC10") (pin "2") (pinfunction "I1_2") (pintype "input"))
      (node (ref "IC19") (pin "2") (pinfunction "I1_2") (pintype "input"))
      (node (ref "IC5") (pin "4") (pinfunction "Q_4") (pintype "output"))
      (node (ref "IC6") (pin "2") (pinfunction "I_2") (pintype "input"))
    )
    (net (code "58") (name "TDONE") (class "Default")
      (node (ref "IC10") (pin "1") (pinfunction "I0_1") (pintype "input"))
      (node (ref "IC14") (pin "4") (pinfunction "Q_4") (pintype "output"))
      (node (ref "IC17") (pin "2") (pinfunction "I_2") (pintype "input"))
      (node (ref "R2") (pin "2") (pinfunction "2_2") (pintype "passive"))
    )
    (net (code "59") (name "THREE") (class "Default")
      (node (ref "D1") (pin "A") (pinfunction "A_A") (pintype "passive"))
      (node (ref "JP5") (pin "5") (pinfunction "5_5") (pintype "passive"))
    )
    (net (code "60") (name "TWO") (class "Default")
      (node (ref "D3") (pin "A") (pinfunction "A_A") (pintype "passive"))
      (node (ref "JP5") (pin "4") (pinfunction "4_4") (pintype "passive"))
    )
    (net (code "61") (name "VCC") (class "Default")
      (node (ref "C10") (pin "1") (pinfunction "1_1") (pintype "passive"))
      (node (ref "C11") (pin "1") (pinfunction "1_1") (pintype "passive"))
      (node (ref "C12") (pin "1") (pinfunction "1_1") (pintype "passive"))
      (node (ref "C13") (pin "1") (pinfunction "1_1") (pintype "passive"))
      (node (ref "C14") (pin "1") (pinfunction "1_1") (pintype "passive"))
      (node (ref "C15") (pin "1") (pinfunction "1_1") (pintype "passive"))
      (node (ref "C16") (pin "1") (pinfunction "1_1") (pintype "passive"))
      (node (ref "C17") (pin "1") (pinfunction "1_1") (pintype "passive"))
      (node (ref "C18") (pin "1") (pinfunction "1_1") (pintype "passive"))
      (node (ref "C19") (pin "1") (pinfunction "1_1") (pintype "passive"))
      (node (ref "C20") (pin "1") (pinfunction "1_1") (pintype "passive"))
      (node (ref "C21") (pin "1") (pinfunction "1_1") (pintype "passive"))
      (node (ref "C22") (pin "1") (pinfunction "1_1") (pintype "passive"))
      (node (ref "C23") (pin "1") (pinfunction "1_1") (pintype "passive"))
      (node (ref "C24") (pin "1") (pinfunction "1_1") (pintype "passive"))
      (node (ref "C25") (pin "A") (pinfunction "+_A") (pintype "passive"))
      (node (ref "C26") (pin "1") (pinfunction "1_1") (pintype "passive"))
      (node (ref "C27") (pin "1") (pinfunction "1_1") (pintype "passive"))
      (node (ref "C3") (pin "1") (pinfunction "1_1") (pintype "passive"))
      (node (ref "C4") (pin "1") (pinfunction "1_1") (pintype "passive"))
      (node (ref "C5") (pin "1") (pinfunction "1_1") (pintype "passive"))
      (node (ref "C6") (pin "1") (pinfunction "1_1") (pintype "passive"))
      (node (ref "C7") (pin "1") (pinfunction "1_1") (pintype "passive"))
      (node (ref "C8") (pin "1") (pinfunction "1_1") (pintype "passive"))
      (node (ref "C9") (pin "1") (pinfunction "1_1") (pintype "passive"))
      (node (ref "IC15") (pin "3") (pinfunction "D_3") (pintype "input"))
      (node (ref "IC22") (pin "3") (pinfunction "D_3") (pintype "input"))
      (node (ref "IC4") (pin "4") (pinfunction "R_4") (pintype "input"))
      (node (ref "IC4") (pin "8") (pinfunction "V+_8") (pintype "power_in"))
      (node (ref "IC8") (pin "3") (pinfunction "D_3") (pintype "input"))
      (node (ref "IC9") (pin "3") (pinfunction "D_3") (pintype "input"))
      (node (ref "J1") (pin "PWR") (pinfunction "PWR_PWR") (pintype "bidirectional"))
      (node (ref "JP1") (pin "1") (pinfunction "1_1") (pintype "passive"))
      (node (ref "JP2") (pin "1") (pinfunction "1_1") (pintype "passive"))
      (node (ref "JP4") (pin "1") (pinfunction "1_1") (pintype "passive"))
      (node (ref "Q6") (pin "E") (pinfunction "E_E") (pintype "passive"))
      (node (ref "R10") (pin "1") (pinfunction "1_1") (pintype "passive"))
      (node (ref "R11") (pin "1") (pinfunction "1_1") (pintype "passive"))
      (node (ref "R14") (pin "2") (pinfunction "2_2") (pintype "passive"))
      (node (ref "R16") (pin "1") (pinfunction "1_1") (pintype "passive"))
      (node (ref "R19") (pin "1") (pinfunction "1_1") (pintype "passive"))
      (node (ref "R21") (pin "1") (pinfunction "1_1") (pintype "passive"))
      (node (ref "R23") (pin "1") (pinfunction "1_1") (pintype "passive"))
      (node (ref "R3") (pin "1") (pinfunction "1_1") (pintype "passive"))
      (node (ref "R4") (pin "1") (pinfunction "1_1") (pintype "passive"))
      (node (ref "R7") (pin "2") (pinfunction "2_2") (pintype "passive"))
    )
    (net (code "62") (name "ZC") (class "Default")
      (node (ref "IC8") (pin "1") (pinfunction "CLK_1") (pintype "input"))
      (node (ref "JP2") (pin "3") (pinfunction "3_3") (pintype "passive"))
    )
    (net (code "63") (name "ZERO") (class "Default")
      (node (ref "JP5") (pin "2") (pinfunction "2_2") (pintype "passive"))
    )
    (net (code "64") (name "unconnected-(IC4-CV-Pad5)") (class "Default")
      (node (ref "IC4") (pin "5") (pinfunction "CV_5") (pintype "input"))
    )
    (net (code "65") (name "unconnected-(JP3-Pad5)") (class "Default")
      (node (ref "JP3") (pin "5") (pinfunction "5_5") (pintype "passive"))
    )
    (net (code "66") (name "unconnected-(S1-O-Pad1)") (class "Default")
      (node (ref "S1") (pin "1") (pinfunction "O_1") (pintype "passive"))
    )
    (net (code "67") (name "~{EXE}") (class "Default")
      (node (ref "C1") (pin "1") (pinfunction "1_1") (pintype "passive"))
      (node (ref "IC3") (pin "2") (pinfunction "I_2") (pintype "input"))
      (node (ref "JP4") (pin "3") (pinfunction "3_3") (pintype "passive"))
      (node (ref "R7") (pin "1") (pinfunction "1_1") (pintype "passive"))
    )
    (net (code "68") (name "~{MCLK}") (class "Default")
      (node (ref "IC11") (pin "2") (pinfunction "I1_2") (pintype "input"))
      (node (ref "IC12") (pin "1") (pinfunction "CLK_1") (pintype "input"))
      (node (ref "IC13") (pin "1") (pinfunction "CLK_1") (pintype "input"))
      (node (ref "IC14") (pin "1") (pinfunction "CLK_1") (pintype "input"))
      (node (ref "IC16") (pin "1") (pinfunction "CLK_1") (pintype "input"))
      (node (ref "IC7") (pin "4") (pinfunction "O_4") (pintype "output"))
      (node (ref "JP3") (pin "2") (pinfunction "2_2") (pintype "passive"))
    )
    (net (code "69") (name "~{RST}") (class "Default")
      (node (ref "IC12") (pin "6") (pinfunction "~{CLR}_6") (pintype "input"))
      (node (ref "IC13") (pin "6") (pinfunction "~{CLR}_6") (pintype "input"))
      (node (ref "IC14") (pin "6") (pinfunction "~{CLR}_6") (pintype "input"))
      (node (ref "IC15") (pin "6") (pinfunction "~{CLR}_6") (pintype "input"))
      (node (ref "IC16") (pin "6") (pinfunction "~{CLR}_6") (pintype "input"))
      (node (ref "IC22") (pin "6") (pinfunction "~{CLR}_6") (pintype "input"))
      (node (ref "IC3") (pin "4") (pinfunction "O_4") (pintype "output"))
      (node (ref "IC5") (pin "6") (pinfunction "~{CLR}_6") (pintype "input"))
      (node (ref "IC8") (pin "6") (pinfunction "~{CLR}_6") (pintype "input"))
      (node (ref "IC9") (pin "6") (pinfunction "~{CLR}_6") (pintype "input"))
      (node (ref "JP3") (pin "1") (pinfunction "1_1") (pintype "passive"))
      (node (ref "JP3") (pin "8") (pinfunction "8_8") (pintype "passive"))
    )
  )
)
